# OneButton.net
KiCad netlist of a schematic drawn in EAGLE
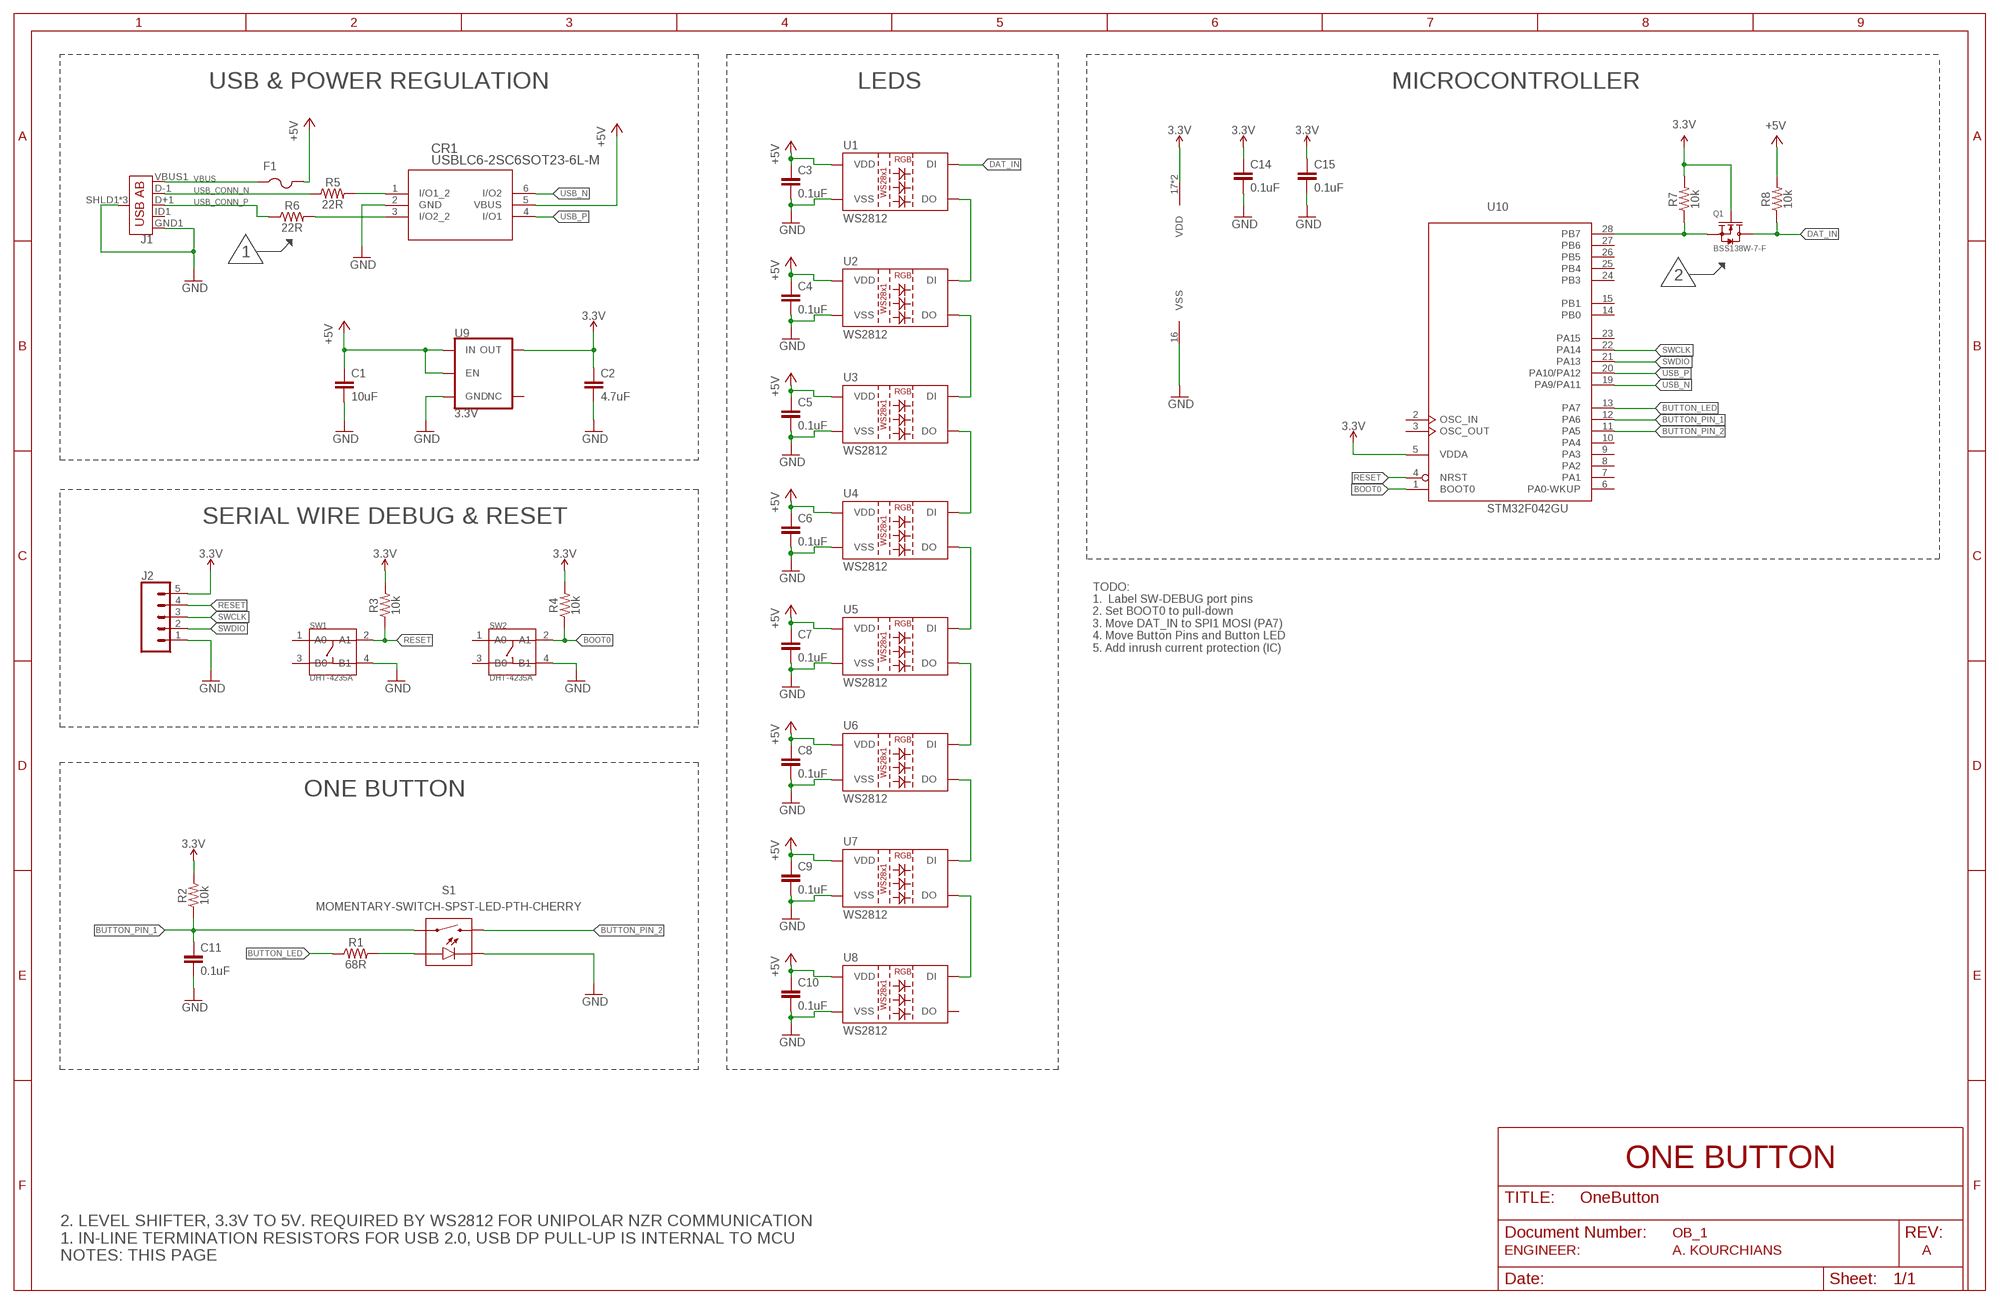
[diagram p0: schematic, sheet 1]

(export (version "E")
  (design (tool "Eeschema 10.0.6"))
  (components
    (comp (ref "C1")
      (value "10uF")
      (footprint "eagle-import:CAP-1206")
      (fields (field (name "MPN") "CL31B106KAHNNNE"))
      (libsource (lib "eagle-import") (part "10UFCAP-1206"))
    )
    (comp (ref "C2")
      (value "4.7uF")
      (footprint "eagle-import:CAP-1206")
      (fields (field (name "MPN") "C3216X7R1C475K160AB"))
      (libsource (lib "eagle-import") (part "4.7UFCAP-1206"))
    )
    (comp (ref "C3")
      (value "0.1uF")
      (footprint "eagle-import:CAP-0603")
      (fields (field (name "MPN") "C0603C104K8RACTU"))
      (libsource (lib "eagle-import") (part "0.1UFCAP-0603"))
    )
    (comp (ref "C4")
      (value "0.1uF")
      (footprint "eagle-import:CAP-0603")
      (fields (field (name "MPN") "C0603C104K8RACTU"))
      (libsource (lib "eagle-import") (part "0.1UFCAP-0603"))
    )
    (comp (ref "C5")
      (value "0.1uF")
      (footprint "eagle-import:CAP-0603")
      (fields (field (name "MPN") "C0603C104K8RACTU"))
      (libsource (lib "eagle-import") (part "0.1UFCAP-0603"))
    )
    (comp (ref "C6")
      (value "0.1uF")
      (footprint "eagle-import:CAP-0603")
      (fields (field (name "MPN") "C0603C104K8RACTU"))
      (libsource (lib "eagle-import") (part "0.1UFCAP-0603"))
    )
    (comp (ref "C7")
      (value "0.1uF")
      (footprint "eagle-import:CAP-0603")
      (fields (field (name "MPN") "C0603C104K8RACTU"))
      (libsource (lib "eagle-import") (part "0.1UFCAP-0603"))
    )
    (comp (ref "C8")
      (value "0.1uF")
      (footprint "eagle-import:CAP-0603")
      (fields (field (name "MPN") "C0603C104K8RACTU"))
      (libsource (lib "eagle-import") (part "0.1UFCAP-0603"))
    )
    (comp (ref "C9")
      (value "0.1uF")
      (footprint "eagle-import:CAP-0603")
      (fields (field (name "MPN") "C0603C104K8RACTU"))
      (libsource (lib "eagle-import") (part "0.1UFCAP-0603"))
    )
    (comp (ref "C10")
      (value "0.1uF")
      (footprint "eagle-import:CAP-0603")
      (fields (field (name "MPN") "C0603C104K8RACTU"))
      (libsource (lib "eagle-import") (part "0.1UFCAP-0603"))
    )
    (comp (ref "C11")
      (value "0.1uF")
      (footprint "eagle-import:CAP-0603")
      (libsource (lib "eagle-import") (part "CAPACITORCAP-0603"))
    )
    (comp (ref "C14")
      (value "0.1uF")
      (footprint "eagle-import:CAP-0603")
      (fields (field (name "MPN") "C0603C104K8RACTU"))
      (libsource (lib "eagle-import") (part "0.1UFCAP-0603"))
    )
    (comp (ref "C15")
      (value "0.1uF")
      (footprint "eagle-import:CAP-0603")
      (fields (field (name "MPN") "C0603C104K8RACTU"))
      (libsource (lib "eagle-import") (part "0.1UFCAP-0603"))
    )
    (comp (ref "CR1")
      (value "USBLC6-2SC6SOT23-6L-M")
      (footprint "eagle-import:SOT23-6L-M")
      (fields (field (name "MPN") "USBLC62SC6"))
      (libsource (lib "eagle-import") (part "USBLC6-2SC6SOT23-6L-M"))
    )
    (comp (ref "F1")
      (value "PTCFUSE-1206")
      (footprint "eagle-import:R1206")
      (fields (field (name "MPN") "0ZCJ0075AF2E"))
      (libsource (lib "eagle-import") (part "PTCFUSE-1206"))
    )
    (comp (ref "J1")
      (value "USB_AB_SMT")
      (footprint "eagle-import:USB-AB-MICRO-SMD")
      (fields (field (name "MPN") "10118192-0001LF"))
      (libsource (lib "eagle-import") (part "USB_AB_SMT"))
    )
    (comp (ref "J2")
      (value "CONN_05")
      (footprint "eagle-import:1X05")
      (fields (field (name "MPN") "61300511121"))
      (libsource (lib "eagle-import") (part "CONN_05"))
    )
    (comp (ref "Q1")
      (value "BSS138W-7-F")
      (footprint "eagle-import:SOT-23")
      (fields (field (name "MPN") "BSS138LT1G"))
      (libsource (lib "eagle-import") (part "SMD-MOSFET-N-CH-50V-200MA-BSS138W-7-F(SOT-23)"))
    )
    (comp (ref "R1")
      (value "68R")
      (footprint "eagle-import:RESC0603_N")
      (libsource (lib "eagle-import") (part "RESISTORRES-0603"))
    )
    (comp (ref "R2")
      (value "10k")
      (footprint "eagle-import:RESC0603_N")
      (libsource (lib "eagle-import") (part "RESISTORRES-0603"))
    )
    (comp (ref "R3")
      (value "10k")
      (footprint "eagle-import:RESC0603_N")
      (libsource (lib "eagle-import") (part "RESISTORRES-0603"))
    )
    (comp (ref "R4")
      (value "10k")
      (footprint "eagle-import:RESC0603_N")
      (libsource (lib "eagle-import") (part "RESISTORRES-0603"))
    )
    (comp (ref "R5")
      (value "22R")
      (footprint "eagle-import:RESC0603_N")
      (libsource (lib "eagle-import") (part "RESISTORRES-0603"))
    )
    (comp (ref "R6")
      (value "22R")
      (footprint "eagle-import:RESC0603_N")
      (libsource (lib "eagle-import") (part "RESISTORRES-0603"))
    )
    (comp (ref "R7")
      (value "10k")
      (footprint "eagle-import:RESC0603_N")
      (libsource (lib "eagle-import") (part "RESISTORRES-0603"))
    )
    (comp (ref "R8")
      (value "10k")
      (footprint "eagle-import:RESC0603_N")
      (libsource (lib "eagle-import") (part "RESISTORRES-0603"))
    )
    (comp (ref "S1")
      (value "MOMENTARY-SWITCH-SPST-LED-PTH-CHERRY")
      (footprint "eagle-import:CHERRY-MX-LED")
      (fields (field (name "MPN") "MX1A-E1NW") (field (name "SPICEPREFIX") "S"))
      (libsource (lib "eagle-import") (part "MOMENTARY-SWITCH-SPST-LED-PTH-CHERRY"))
    )
    (comp (ref "SW1")
      (value "DHT-4235A")
      (footprint "eagle-import:SW4-SMD-4.2X3.2X2.5MM")
      (fields (field (name "MPN") "PTS810 SJK 250 SMTR LFS"))
      (libsource (lib "eagle-import") (part "SMD-BUTTON-TOP-DHT-4235A(4P-4.2X3.2MM)"))
    )
    (comp (ref "SW2")
      (value "DHT-4235A")
      (footprint "eagle-import:SW4-SMD-4.2X3.2X2.5MM")
      (fields (field (name "MPN") "PTS810 SJK 250 SMTR LFS"))
      (libsource (lib "eagle-import") (part "SMD-BUTTON-TOP-DHT-4235A(4P-4.2X3.2MM)"))
    )
    (comp (ref "U1")
      (value "WS2812")
      (footprint "eagle-import:LED-TRICOLOR-5050-IC")
      (libsource (lib "eagle-import") (part "WS2812{dblquote}"))
    )
    (comp (ref "U2")
      (value "WS2812")
      (footprint "eagle-import:LED-TRICOLOR-5050-IC")
      (libsource (lib "eagle-import") (part "WS2812{dblquote}"))
    )
    (comp (ref "U3")
      (value "WS2812")
      (footprint "eagle-import:LED-TRICOLOR-5050-IC")
      (libsource (lib "eagle-import") (part "WS2812{dblquote}"))
    )
    (comp (ref "U4")
      (value "WS2812")
      (footprint "eagle-import:LED-TRICOLOR-5050-IC")
      (libsource (lib "eagle-import") (part "WS2812{dblquote}"))
    )
    (comp (ref "U5")
      (value "WS2812")
      (footprint "eagle-import:LED-TRICOLOR-5050-IC")
      (libsource (lib "eagle-import") (part "WS2812{dblquote}"))
    )
    (comp (ref "U6")
      (value "WS2812")
      (footprint "eagle-import:LED-TRICOLOR-5050-IC")
      (libsource (lib "eagle-import") (part "WS2812{dblquote}"))
    )
    (comp (ref "U7")
      (value "WS2812")
      (footprint "eagle-import:LED-TRICOLOR-5050-IC")
      (libsource (lib "eagle-import") (part "WS2812{dblquote}"))
    )
    (comp (ref "U8")
      (value "WS2812")
      (footprint "eagle-import:LED-TRICOLOR-5050-IC")
      (libsource (lib "eagle-import") (part "WS2812{dblquote}"))
    )
    (comp (ref "U9")
      (value "3.3V")
      (footprint "eagle-import:SOT23-5")
      (fields (field (name "MPN") "AP2112K-3.3TRG1"))
      (libsource (lib "eagle-import") (part "V_REG_AP2112K-3.3V"))
    )
    (comp (ref "U10")
      (value "STM32F042GU")
      (footprint "eagle-import:UFQFPN28")
      (fields (field (name "MPN") "STM32F042G6U6"))
      (libsource (lib "eagle-import") (part "STM32F042GU"))
    )
  )
  (nets
    (net (code "1") (name "+5V") (class "Default")
      (node (ref "C1") (pin "1") (pinfunction "1_1") (pintype "passive"))
      (node (ref "C10") (pin "1") (pinfunction "1_1") (pintype "passive"))
      (node (ref "C3") (pin "1") (pinfunction "1_1") (pintype "passive"))
      (node (ref "C4") (pin "1") (pinfunction "1_1") (pintype "passive"))
      (node (ref "C5") (pin "1") (pinfunction "1_1") (pintype "passive"))
      (node (ref "C6") (pin "1") (pinfunction "1_1") (pintype "passive"))
      (node (ref "C7") (pin "1") (pinfunction "1_1") (pintype "passive"))
      (node (ref "C8") (pin "1") (pinfunction "1_1") (pintype "passive"))
      (node (ref "C9") (pin "1") (pinfunction "1_1") (pintype "passive"))
      (node (ref "CR1") (pin "5") (pinfunction "VBUS_5") (pintype "power_in"))
      (node (ref "F1") (pin "2") (pinfunction "2_2") (pintype "passive"))
      (node (ref "R8") (pin "2") (pinfunction "2_2") (pintype "passive"))
      (node (ref "U1") (pin "3") (pinfunction "VDD_3") (pintype "bidirectional"))
      (node (ref "U1") (pin "5") (pinfunction "VDD_5") (pintype "bidirectional"))
      (node (ref "U2") (pin "3") (pinfunction "VDD_3") (pintype "bidirectional"))
      (node (ref "U2") (pin "5") (pinfunction "VDD_5") (pintype "bidirectional"))
      (node (ref "U3") (pin "3") (pinfunction "VDD_3") (pintype "bidirectional"))
      (node (ref "U3") (pin "5") (pinfunction "VDD_5") (pintype "bidirectional"))
      (node (ref "U4") (pin "3") (pinfunction "VDD_3") (pintype "bidirectional"))
      (node (ref "U4") (pin "5") (pinfunction "VDD_5") (pintype "bidirectional"))
      (node (ref "U5") (pin "3") (pinfunction "VDD_3") (pintype "bidirectional"))
      (node (ref "U5") (pin "5") (pinfunction "VDD_5") (pintype "bidirectional"))
      (node (ref "U6") (pin "3") (pinfunction "VDD_3") (pintype "bidirectional"))
      (node (ref "U6") (pin "5") (pinfunction "VDD_5") (pintype "bidirectional"))
      (node (ref "U7") (pin "3") (pinfunction "VDD_3") (pintype "bidirectional"))
      (node (ref "U7") (pin "5") (pinfunction "VDD_5") (pintype "bidirectional"))
      (node (ref "U8") (pin "3") (pinfunction "VDD_3") (pintype "bidirectional"))
      (node (ref "U8") (pin "5") (pinfunction "VDD_5") (pintype "bidirectional"))
      (node (ref "U9") (pin "1") (pinfunction "IN_1") (pintype "input"))
      (node (ref "U9") (pin "3") (pinfunction "EN_3") (pintype "input"))
    )
    (net (code "2") (name "/USB_CONN_N") (class "Default")
      (node (ref "J1") (pin "D-1") (pinfunction "D-_D-1") (pintype "bidirectional"))
      (node (ref "R5") (pin "1") (pinfunction "1_1") (pintype "passive"))
    )
    (net (code "3") (name "/USB_CONN_P") (class "Default")
      (node (ref "J1") (pin "D+1") (pinfunction "D+_D+1") (pintype "bidirectional"))
      (node (ref "R6") (pin "1") (pinfunction "1_1") (pintype "passive"))
    )
    (net (code "4") (name "/VBUS") (class "Default")
      (node (ref "F1") (pin "1") (pinfunction "1_1") (pintype "passive"))
      (node (ref "J1") (pin "VBUS1") (pinfunction "VBUS_VBUS1") (pintype "power_in"))
    )
    (net (code "5") (name "3.3V") (class "Default")
      (node (ref "C14") (pin "1") (pinfunction "1_1") (pintype "passive"))
      (node (ref "C15") (pin "1") (pinfunction "1_1") (pintype "passive"))
      (node (ref "C2") (pin "1") (pinfunction "1_1") (pintype "passive"))
      (node (ref "J2") (pin "5") (pinfunction "5_5") (pintype "passive"))
      (node (ref "Q1") (pin "1") (pinfunction "G_1") (pintype "passive"))
      (node (ref "R2") (pin "2") (pinfunction "2_2") (pintype "passive"))
      (node (ref "R3") (pin "2") (pinfunction "2_2") (pintype "passive"))
      (node (ref "R4") (pin "2") (pinfunction "2_2") (pintype "passive"))
      (node (ref "R7") (pin "2") (pinfunction "2_2") (pintype "passive"))
      (node (ref "U10") (pin "17") (pinfunction "VDD_17") (pintype "power_in"))
      (node (ref "U10") (pin "18") (pinfunction "VDD_18") (pintype "power_in"))
      (node (ref "U10") (pin "5") (pinfunction "VDDA_5") (pintype "power_in"))
      (node (ref "U9") (pin "5") (pinfunction "OUT_5") (pintype "passive"))
    )
    (net (code "6") (name "BOOT0") (class "Default")
      (node (ref "R4") (pin "1") (pinfunction "1_1") (pintype "passive"))
      (node (ref "SW2") (pin "2") (pinfunction "A1_2") (pintype "bidirectional"))
      (node (ref "U10") (pin "1") (pinfunction "BOOT0_1") (pintype "input"))
    )
    (net (code "7") (name "BUTTON_LED") (class "Default")
      (node (ref "R1") (pin "1") (pinfunction "1_1") (pintype "passive"))
      (node (ref "U10") (pin "13") (pinfunction "PA7_13") (pintype "bidirectional"))
    )
    (net (code "8") (name "BUTTON_PIN_1") (class "Default")
      (node (ref "C11") (pin "1") (pinfunction "1_1") (pintype "passive"))
      (node (ref "R2") (pin "1") (pinfunction "1_1") (pintype "passive"))
      (node (ref "S1") (pin "S1") (pinfunction "1_S1") (pintype "passive"))
      (node (ref "U10") (pin "12") (pinfunction "PA6_12") (pintype "bidirectional"))
    )
    (net (code "9") (name "BUTTON_PIN_2") (class "Default")
      (node (ref "S1") (pin "S2") (pinfunction "2_S2") (pintype "passive"))
      (node (ref "U10") (pin "11") (pinfunction "PA5_11") (pintype "bidirectional"))
    )
    (net (code "10") (name "DAT_IN") (class "Default")
      (node (ref "Q1") (pin "3") (pinfunction "D_3") (pintype "passive"))
      (node (ref "R8") (pin "1") (pinfunction "1_1") (pintype "passive"))
      (node (ref "U1") (pin "2") (pinfunction "DI_2") (pintype "bidirectional"))
    )
    (net (code "11") (name "GND") (class "Default")
      (node (ref "C1") (pin "2") (pinfunction "2_2") (pintype "passive"))
      (node (ref "C10") (pin "2") (pinfunction "2_2") (pintype "passive"))
      (node (ref "C11") (pin "2") (pinfunction "2_2") (pintype "passive"))
      (node (ref "C14") (pin "2") (pinfunction "2_2") (pintype "passive"))
      (node (ref "C15") (pin "2") (pinfunction "2_2") (pintype "passive"))
      (node (ref "C2") (pin "2") (pinfunction "2_2") (pintype "passive"))
      (node (ref "C3") (pin "2") (pinfunction "2_2") (pintype "passive"))
      (node (ref "C4") (pin "2") (pinfunction "2_2") (pintype "passive"))
      (node (ref "C5") (pin "2") (pinfunction "2_2") (pintype "passive"))
      (node (ref "C6") (pin "2") (pinfunction "2_2") (pintype "passive"))
      (node (ref "C7") (pin "2") (pinfunction "2_2") (pintype "passive"))
      (node (ref "C8") (pin "2") (pinfunction "2_2") (pintype "passive"))
      (node (ref "C9") (pin "2") (pinfunction "2_2") (pintype "passive"))
      (node (ref "CR1") (pin "2") (pinfunction "GND_2") (pintype "power_in"))
      (node (ref "J1") (pin "GND1") (pinfunction "GND_GND1") (pintype "power_in"))
      (node (ref "J1") (pin "SHLD1") (pinfunction "SHIELD_SHLD1") (pintype "bidirectional"))
      (node (ref "J1") (pin "SHLD2") (pinfunction "SHIELD_SHLD2") (pintype "bidirectional"))
      (node (ref "J1") (pin "SHLD3") (pinfunction "SHIELD_SHLD3") (pintype "bidirectional"))
      (node (ref "J2") (pin "1") (pinfunction "1_1") (pintype "passive"))
      (node (ref "S1") (pin "K") (pinfunction "C_K") (pintype "passive"))
      (node (ref "S1") (pin "K1") (pinfunction "C_K1") (pintype "passive"))
      (node (ref "SW1") (pin "4") (pinfunction "B1_4") (pintype "bidirectional"))
      (node (ref "SW2") (pin "4") (pinfunction "B1_4") (pintype "bidirectional"))
      (node (ref "U1") (pin "6") (pinfunction "VSS_6") (pintype "bidirectional"))
      (node (ref "U10") (pin "16") (pinfunction "VSS_16") (pintype "power_in"))
      (node (ref "U2") (pin "6") (pinfunction "VSS_6") (pintype "bidirectional"))
      (node (ref "U3") (pin "6") (pinfunction "VSS_6") (pintype "bidirectional"))
      (node (ref "U4") (pin "6") (pinfunction "VSS_6") (pintype "bidirectional"))
      (node (ref "U5") (pin "6") (pinfunction "VSS_6") (pintype "bidirectional"))
      (node (ref "U6") (pin "6") (pinfunction "VSS_6") (pintype "bidirectional"))
      (node (ref "U7") (pin "6") (pinfunction "VSS_6") (pintype "bidirectional"))
      (node (ref "U8") (pin "6") (pinfunction "VSS_6") (pintype "bidirectional"))
      (node (ref "U9") (pin "2") (pinfunction "GND_2") (pintype "input"))
    )
    (net (code "12") (name "Net-(CR1-I{slash}O1_2)") (class "Default")
      (node (ref "CR1") (pin "1") (pinfunction "I/O1_2_1") (pintype "bidirectional"))
      (node (ref "R5") (pin "2") (pinfunction "2_2") (pintype "passive"))
    )
    (net (code "13") (name "Net-(CR1-I{slash}O2_2)") (class "Default")
      (node (ref "CR1") (pin "3") (pinfunction "I/O2_2_3") (pintype "bidirectional"))
      (node (ref "R6") (pin "2") (pinfunction "2_2") (pintype "passive"))
    )
    (net (code "14") (name "Net-(Q1-S)") (class "Default")
      (node (ref "Q1") (pin "2") (pinfunction "S_2") (pintype "passive"))
      (node (ref "R7") (pin "1") (pinfunction "1_1") (pintype "passive"))
      (node (ref "U10") (pin "28") (pinfunction "PB7_28") (pintype "bidirectional"))
    )
    (net (code "15") (name "Net-(R1-Pad2)") (class "Default")
      (node (ref "R1") (pin "2") (pinfunction "2_2") (pintype "passive"))
      (node (ref "S1") (pin "A") (pinfunction "A_A") (pintype "passive"))
      (node (ref "S1") (pin "A1") (pinfunction "A_A1") (pintype "passive"))
    )
    (net (code "16") (name "Net-(U1-DO)") (class "Default")
      (node (ref "U1") (pin "1") (pinfunction "DO_1") (pintype "bidirectional"))
      (node (ref "U2") (pin "2") (pinfunction "DI_2") (pintype "bidirectional"))
    )
    (net (code "17") (name "Net-(U2-DO)") (class "Default")
      (node (ref "U2") (pin "1") (pinfunction "DO_1") (pintype "bidirectional"))
      (node (ref "U3") (pin "2") (pinfunction "DI_2") (pintype "bidirectional"))
    )
    (net (code "18") (name "Net-(U3-DO)") (class "Default")
      (node (ref "U3") (pin "1") (pinfunction "DO_1") (pintype "bidirectional"))
      (node (ref "U4") (pin "2") (pinfunction "DI_2") (pintype "bidirectional"))
    )
    (net (code "19") (name "Net-(U4-DO)") (class "Default")
      (node (ref "U4") (pin "1") (pinfunction "DO_1") (pintype "bidirectional"))
      (node (ref "U5") (pin "2") (pinfunction "DI_2") (pintype "bidirectional"))
    )
    (net (code "20") (name "Net-(U5-DO)") (class "Default")
      (node (ref "U5") (pin "1") (pinfunction "DO_1") (pintype "bidirectional"))
      (node (ref "U6") (pin "2") (pinfunction "DI_2") (pintype "bidirectional"))
    )
    (net (code "21") (name "Net-(U6-DO)") (class "Default")
      (node (ref "U6") (pin "1") (pinfunction "DO_1") (pintype "bidirectional"))
      (node (ref "U7") (pin "2") (pinfunction "DI_2") (pintype "bidirectional"))
    )
    (net (code "22") (name "Net-(U7-DO)") (class "Default")
      (node (ref "U7") (pin "1") (pinfunction "DO_1") (pintype "bidirectional"))
      (node (ref "U8") (pin "2") (pinfunction "DI_2") (pintype "bidirectional"))
    )
    (net (code "23") (name "RESET") (class "Default")
      (node (ref "J2") (pin "4") (pinfunction "4_4") (pintype "passive"))
      (node (ref "R3") (pin "1") (pinfunction "1_1") (pintype "passive"))
      (node (ref "SW1") (pin "2") (pinfunction "A1_2") (pintype "bidirectional"))
      (node (ref "U10") (pin "4") (pinfunction "NRST_4") (pintype "bidirectional"))
    )
    (net (code "24") (name "SWCLK") (class "Default")
      (node (ref "J2") (pin "3") (pinfunction "3_3") (pintype "passive"))
      (node (ref "U10") (pin "22") (pinfunction "PA14_22") (pintype "bidirectional"))
    )
    (net (code "25") (name "SWDIO") (class "Default")
      (node (ref "J2") (pin "2") (pinfunction "2_2") (pintype "passive"))
      (node (ref "U10") (pin "21") (pinfunction "PA13_21") (pintype "bidirectional"))
    )
    (net (code "26") (name "USB_N") (class "Default")
      (node (ref "CR1") (pin "6") (pinfunction "I/O2_6") (pintype "bidirectional"))
      (node (ref "U10") (pin "19") (pinfunction "PA9/PA11_19") (pintype "bidirectional"))
    )
    (net (code "27") (name "USB_P") (class "Default")
      (node (ref "CR1") (pin "4") (pinfunction "I/O1_4") (pintype "bidirectional"))
      (node (ref "U10") (pin "20") (pinfunction "PA10/PA12_20") (pintype "bidirectional"))
    )
    (net (code "28") (name "unconnected-(J1-USBID-PadID1)") (class "Default")
      (node (ref "J1") (pin "ID1") (pinfunction "USBID_ID1") (pintype "bidirectional"))
    )
    (net (code "29") (name "unconnected-(SW1-A0-Pad1)") (class "Default")
      (node (ref "SW1") (pin "1") (pinfunction "A0_1") (pintype "bidirectional"))
    )
    (net (code "30") (name "unconnected-(SW1-B0-Pad3)") (class "Default")
      (node (ref "SW1") (pin "3") (pinfunction "B0_3") (pintype "bidirectional"))
    )
    (net (code "31") (name "unconnected-(SW2-A0-Pad1)") (class "Default")
      (node (ref "SW2") (pin "1") (pinfunction "A0_1") (pintype "bidirectional"))
    )
    (net (code "32") (name "unconnected-(SW2-B0-Pad3)") (class "Default")
      (node (ref "SW2") (pin "3") (pinfunction "B0_3") (pintype "bidirectional"))
    )
    (net (code "33") (name "unconnected-(U8-DO-Pad1)") (class "Default")
      (node (ref "U8") (pin "1") (pinfunction "DO_1") (pintype "bidirectional"))
    )
    (net (code "34") (name "unconnected-(U9-NC-Pad4)") (class "Default")
      (node (ref "U9") (pin "4") (pinfunction "NC_4") (pintype "no_connect"))
    )
    (net (code "35") (name "unconnected-(U10A-OSC_IN-Pad2)") (class "Default")
      (node (ref "U10") (pin "2") (pinfunction "OSC_IN_2") (pintype "bidirectional"))
    )
    (net (code "36") (name "unconnected-(U10A-OSC_OUT-Pad3)") (class "Default")
      (node (ref "U10") (pin "3") (pinfunction "OSC_OUT_3") (pintype "bidirectional"))
    )
    (net (code "37") (name "unconnected-(U10A-PA0-WKUP-Pad6)") (class "Default")
      (node (ref "U10") (pin "6") (pinfunction "PA0-WKUP_6") (pintype "bidirectional"))
    )
    (net (code "38") (name "unconnected-(U10A-PA1-Pad7)") (class "Default")
      (node (ref "U10") (pin "7") (pinfunction "PA1_7") (pintype "bidirectional"))
    )
    (net (code "39") (name "unconnected-(U10A-PA2-Pad8)") (class "Default")
      (node (ref "U10") (pin "8") (pinfunction "PA2_8") (pintype "bidirectional"))
    )
    (net (code "40") (name "unconnected-(U10A-PA3-Pad9)") (class "Default")
      (node (ref "U10") (pin "9") (pinfunction "PA3_9") (pintype "bidirectional"))
    )
    (net (code "41") (name "unconnected-(U10A-PA4-Pad10)") (class "Default")
      (node (ref "U10") (pin "10") (pinfunction "PA4_10") (pintype "bidirectional"))
    )
    (net (code "42") (name "unconnected-(U10A-PA15-Pad23)") (class "Default")
      (node (ref "U10") (pin "23") (pinfunction "PA15_23") (pintype "bidirectional"))
    )
    (net (code "43") (name "unconnected-(U10A-PB0-Pad14)") (class "Default")
      (node (ref "U10") (pin "14") (pinfunction "PB0_14") (pintype "bidirectional"))
    )
    (net (code "44") (name "unconnected-(U10A-PB1-Pad15)") (class "Default")
      (node (ref "U10") (pin "15") (pinfunction "PB1_15") (pintype "bidirectional"))
    )
    (net (code "45") (name "unconnected-(U10A-PB3-Pad24)") (class "Default")
      (node (ref "U10") (pin "24") (pinfunction "PB3_24") (pintype "bidirectional"))
    )
    (net (code "46") (name "unconnected-(U10A-PB4-Pad25)") (class "Default")
      (node (ref "U10") (pin "25") (pinfunction "PB4_25") (pintype "bidirectional"))
    )
    (net (code "47") (name "unconnected-(U10A-PB5-Pad26)") (class "Default")
      (node (ref "U10") (pin "26") (pinfunction "PB5_26") (pintype "bidirectional"))
    )
    (net (code "48") (name "unconnected-(U10A-PB6-Pad27)") (class "Default")
      (node (ref "U10") (pin "27") (pinfunction "PB6_27") (pintype "bidirectional"))
    )
  )
)
